# 99_CAN_Interface.net
KiCad netlist of a schematic drawn in Altium Designer
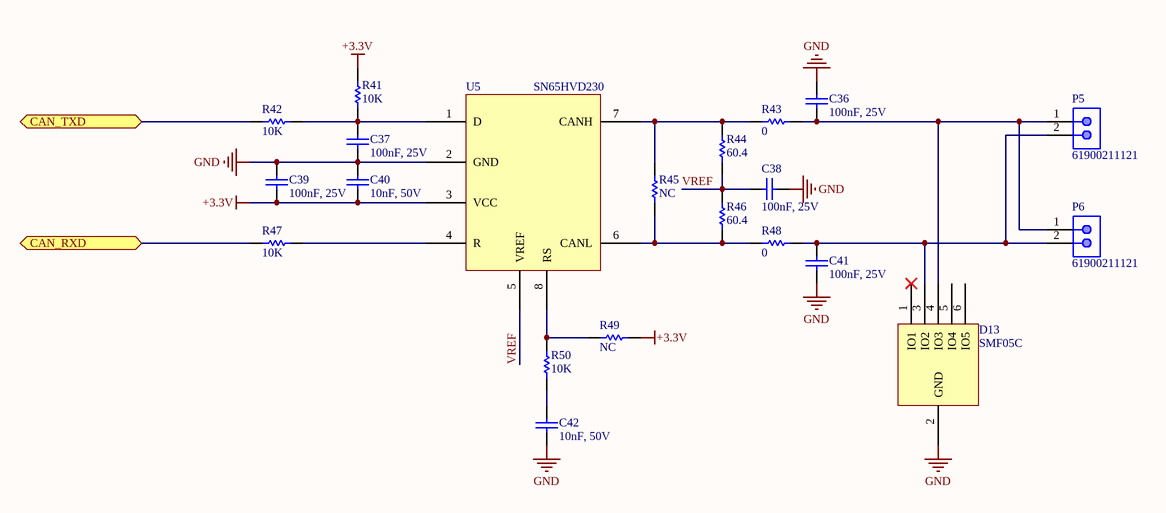
[diagram p0: 99_CAN_Interface.SchDoc]

(export (version "E")
  (design (tool "Eeschema 10.0.6"))
  (components
    (comp (ref "C36")
      (value "100nF, 25V")
      (footprint "WCAP-CSGP_0603_H=0.8mm_Reflow")
      (description "WCAP-CSGP Multilayer Ceramic Chip Capacitor, General Purpose, size 0603, X7R, 100nF, 25V")
      (fields
        (field (name "MANUFACTURER PART NUMBER") "885012206071")
        (field (name "MANUFACTURER") "Wurth Elektronik")
      )
      (libsource (lib "Altium_WCAP-CSGP (rev20a)") (part "885012206071"))
    )
    (comp (ref "C37")
      (value "100nF, 25V")
      (footprint "WCAP-CSGP_0603_H=0.8mm_Reflow")
      (description "WCAP-CSGP Multilayer Ceramic Chip Capacitor, General Purpose, size 0603, X7R, 100nF, 25V")
      (fields
        (field (name "MANUFACTURER PART NUMBER") "885012206071")
        (field (name "MANUFACTURER") "Wurth Elektronik")
      )
      (libsource (lib "Altium_WCAP-CSGP (rev20a)") (part "885012206071"))
    )
    (comp (ref "C38")
      (value "100nF, 25V")
      (footprint "WCAP-CSGP_0603_H=0.8mm_Reflow")
      (description "WCAP-CSGP Multilayer Ceramic Chip Capacitor, General Purpose, size 0603, X7R, 100nF, 25V")
      (fields
        (field (name "MANUFACTURER PART NUMBER") "885012206071")
        (field (name "MANUFACTURER") "Wurth Elektronik")
      )
      (libsource (lib "Altium_WCAP-CSGP (rev20a)") (part "885012206071"))
    )
    (comp (ref "C39")
      (value "100nF, 25V")
      (footprint "WCAP-CSGP_0603_H=0.8mm_Reflow")
      (description "WCAP-CSGP Multilayer Ceramic Chip Capacitor, General Purpose, size 0603, X7R, 100nF, 25V")
      (fields
        (field (name "MANUFACTURER PART NUMBER") "885012206071")
        (field (name "MANUFACTURER") "Wurth Elektronik")
      )
      (libsource (lib "Altium_WCAP-CSGP (rev20a)") (part "885012206071"))
    )
    (comp (ref "C40")
      (value "10nF, 50V")
      (footprint "WCAP-CSGP_0603_H=0.8mm_Reflow")
      (description "WCAP-CSGP Multilayer Ceramic Chip Capacitor, General Purpose, size 0603, X7R, 10nF, 50V")
      (fields
        (field (name "MANUFACTURER PART NUMBER") "885012206089")
        (field (name "MANUFACTURER") "Wurth Elektronik")
      )
      (libsource (lib "Altium_WCAP-CSGP (rev20a)") (part "885012206089"))
    )
    (comp (ref "C41")
      (value "100nF, 25V")
      (footprint "WCAP-CSGP_0603_H=0.8mm_Reflow")
      (description "WCAP-CSGP Multilayer Ceramic Chip Capacitor, General Purpose, size 0603, X7R, 100nF, 25V")
      (fields
        (field (name "MANUFACTURER PART NUMBER") "885012206071")
        (field (name "MANUFACTURER") "Wurth Elektronik")
      )
      (libsource (lib "Altium_WCAP-CSGP (rev20a)") (part "885012206071"))
    )
    (comp (ref "C42")
      (value "10nF, 50V")
      (footprint "WCAP-CSGP_0603_H=0.8mm_Reflow")
      (description "WCAP-CSGP Multilayer Ceramic Chip Capacitor, General Purpose, size 0603, X7R, 10nF, 50V")
      (fields
        (field (name "MANUFACTURER PART NUMBER") "885012206089")
        (field (name "MANUFACTURER") "Wurth Elektronik")
      )
      (libsource (lib "Altium_WCAP-CSGP (rev20a)") (part "885012206089"))
    )
    (comp (ref "D13")
      (value "SMF05C")
      (footprint "SOT65P210X110-6N")
      (libsource (lib "MiclsLib") (part "SMF05C"))
    )
    (comp (ref "P5")
      (value "61900211121")
      (footprint "61900211121")
      (description "WR-WTB THT Male Vertical Locking Header, pitch 2.54mm, 2p")
      (fields (field (name "PUBLISHER") "Wurth Elektronik"))
      (libsource (lib "653008114822_Altium_WR-WTB_rev20a") (part "61900211121"))
    )
    (comp (ref "P6")
      (value "61900211121")
      (footprint "61900211121")
      (description "WR-WTB THT Male Vertical Locking Header, pitch 2.54mm, 2p")
      (fields (field (name "PUBLISHER") "Wurth Elektronik"))
      (libsource (lib "653008114822_Altium_WR-WTB_rev20a") (part "61900211121"))
    )
    (comp (ref "R41")
      (value "10K")
      (footprint "RES-SM-0603")
      (description "Resistor")
      (fields (field (name "Comment") "RESISTOR SMD"))
      (libsource (lib "PIF_Library") (part "RESISTOR SMD"))
    )
    (comp (ref "R42")
      (value "10K")
      (footprint "RES-SM-0603")
      (description "Resistor")
      (fields (field (name "Comment") "RESISTOR SMD"))
      (libsource (lib "PIF_Library") (part "RESISTOR SMD"))
    )
    (comp (ref "R43")
      (value "0")
      (footprint "RES-SM-0603")
      (description "Resistor")
      (fields (field (name "Comment") "RESISTOR SMD"))
      (libsource (lib "PIF_Library") (part "RESISTOR SMD"))
    )
    (comp (ref "R44")
      (value "60.4")
      (footprint "RES-SM-0603")
      (description "Resistor")
      (fields (field (name "Comment") "RESISTOR SMD"))
      (libsource (lib "PIF_Library") (part "RESISTOR SMD"))
    )
    (comp (ref "R45")
      (value "NC")
      (footprint "RES-SM-0603")
      (description "Resistor")
      (fields (field (name "Comment") "RESISTOR SMD"))
      (libsource (lib "PIF_Library") (part "RESISTOR SMD"))
    )
    (comp (ref "R46")
      (value "60.4")
      (footprint "RES-SM-0603")
      (description "Resistor")
      (fields (field (name "Comment") "RESISTOR SMD"))
      (libsource (lib "PIF_Library") (part "RESISTOR SMD"))
    )
    (comp (ref "R47")
      (value "10K")
      (footprint "RES-SM-0603")
      (description "Resistor")
      (fields (field (name "Comment") "RESISTOR SMD"))
      (libsource (lib "PIF_Library") (part "RESISTOR SMD"))
    )
    (comp (ref "R48")
      (value "0")
      (footprint "RES-SM-0603")
      (description "Resistor")
      (fields (field (name "Comment") "RESISTOR SMD"))
      (libsource (lib "PIF_Library") (part "RESISTOR SMD"))
    )
    (comp (ref "R49")
      (value "NC")
      (footprint "RES-SM-0603")
      (description "Resistor")
      (fields (field (name "Comment") "RESISTOR SMD"))
      (libsource (lib "PIF_Library") (part "RESISTOR SMD"))
    )
    (comp (ref "R50")
      (value "10K")
      (footprint "RES-SM-0603")
      (description "Resistor")
      (fields (field (name "Comment") "RESISTOR SMD"))
      (libsource (lib "PIF_Library") (part "RESISTOR SMD"))
    )
    (comp (ref "U5")
      (value "SN65HVD230")
      (footprint "SOIC127P600X175-8N")
      (libsource (lib "MiclsLib") (part "SN65HVD230"))
    )
  )
  (nets
    (net (code "1") (name "+3.3V") (class "Default")
      (node (ref "C39") (pin "1") (pinfunction "1_1") (pintype "passive"))
      (node (ref "C40") (pin "1") (pinfunction "1_1") (pintype "passive"))
      (node (ref "R41") (pin "2") (pinfunction "2_2") (pintype "passive"))
      (node (ref "R49") (pin "1") (pinfunction "1_1") (pintype "passive"))
      (node (ref "U5") (pin "3") (pinfunction "VCC_3") (pintype "passive"))
    )
    (net (code "2") (name "/CAN_RXD") (class "Default")
      (node (ref "R47") (pin "2") (pinfunction "2_2") (pintype "passive"))
    )
    (net (code "3") (name "/CAN_TXD") (class "Default")
      (node (ref "R42") (pin "2") (pinfunction "2_2") (pintype "passive"))
    )
    (net (code "4") (name "/VREF") (class "Default")
      (node (ref "C38") (pin "2") (pinfunction "2_2") (pintype "passive"))
      (node (ref "R44") (pin "2") (pinfunction "2_2") (pintype "passive"))
      (node (ref "R46") (pin "1") (pinfunction "1_1") (pintype "passive"))
      (node (ref "U5") (pin "5") (pinfunction "VREF_5") (pintype "passive"))
    )
    (net (code "5") (name "GND") (class "Default")
      (node (ref "C36") (pin "2") (pinfunction "2_2") (pintype "passive"))
      (node (ref "C37") (pin "1") (pinfunction "1_1") (pintype "passive"))
      (node (ref "C38") (pin "1") (pinfunction "1_1") (pintype "passive"))
      (node (ref "C39") (pin "2") (pinfunction "2_2") (pintype "passive"))
      (node (ref "C40") (pin "2") (pinfunction "2_2") (pintype "passive"))
      (node (ref "C41") (pin "1") (pinfunction "1_1") (pintype "passive"))
      (node (ref "C42") (pin "1") (pinfunction "1_1") (pintype "passive"))
      (node (ref "D13") (pin "2") (pinfunction "GND_2") (pintype "passive"))
      (node (ref "U5") (pin "2") (pinfunction "GND_2") (pintype "passive"))
    )
    (net (code "6") (name "Net-(C42-Pad2)") (class "Default")
      (node (ref "C42") (pin "2") (pinfunction "2_2") (pintype "passive"))
      (node (ref "R50") (pin "1") (pinfunction "1_1") (pintype "passive"))
    )
    (net (code "7") (name "Net-(D13-IO2)") (class "Default")
      (node (ref "C41") (pin "2") (pinfunction "2_2") (pintype "passive"))
      (node (ref "D13") (pin "3") (pinfunction "IO2_3") (pintype "passive"))
      (node (ref "P5") (pin "2") (pinfunction "2_2") (pintype "passive"))
      (node (ref "P6") (pin "2") (pinfunction "2_2") (pintype "passive"))
      (node (ref "R48") (pin "1") (pinfunction "1_1") (pintype "passive"))
    )
    (net (code "8") (name "Net-(D13-IO3)") (class "Default")
      (node (ref "C36") (pin "1") (pinfunction "1_1") (pintype "passive"))
      (node (ref "D13") (pin "4") (pinfunction "IO3_4") (pintype "passive"))
      (node (ref "P5") (pin "1") (pinfunction "1_1") (pintype "passive"))
      (node (ref "P6") (pin "1") (pinfunction "1_1") (pintype "passive"))
      (node (ref "R43") (pin "1") (pinfunction "1_1") (pintype "passive"))
    )
    (net (code "9") (name "Net-(U5-CANH)") (class "Default")
      (node (ref "R43") (pin "2") (pinfunction "2_2") (pintype "passive"))
      (node (ref "R44") (pin "1") (pinfunction "1_1") (pintype "passive"))
      (node (ref "R45") (pin "1") (pinfunction "1_1") (pintype "passive"))
      (node (ref "U5") (pin "7") (pinfunction "CANH_7") (pintype "passive"))
    )
    (net (code "10") (name "Net-(U5-CANL)") (class "Default")
      (node (ref "R45") (pin "2") (pinfunction "2_2") (pintype "passive"))
      (node (ref "R46") (pin "2") (pinfunction "2_2") (pintype "passive"))
      (node (ref "R48") (pin "2") (pinfunction "2_2") (pintype "passive"))
      (node (ref "U5") (pin "6") (pinfunction "CANL_6") (pintype "passive"))
    )
    (net (code "11") (name "Net-(U5-D)") (class "Default")
      (node (ref "C37") (pin "2") (pinfunction "2_2") (pintype "passive"))
      (node (ref "R41") (pin "1") (pinfunction "1_1") (pintype "passive"))
      (node (ref "R42") (pin "1") (pinfunction "1_1") (pintype "passive"))
      (node (ref "U5") (pin "1") (pinfunction "D_1") (pintype "passive"))
    )
    (net (code "12") (name "Net-(U5-R)") (class "Default")
      (node (ref "R47") (pin "1") (pinfunction "1_1") (pintype "passive"))
      (node (ref "U5") (pin "4") (pinfunction "R_4") (pintype "passive"))
    )
    (net (code "13") (name "Net-(U5-RS)") (class "Default")
      (node (ref "R49") (pin "2") (pinfunction "2_2") (pintype "passive"))
      (node (ref "R50") (pin "2") (pinfunction "2_2") (pintype "passive"))
      (node (ref "U5") (pin "8") (pinfunction "RS_8") (pintype "passive"))
    )
    (net (code "14") (name "unconnected-(D13-IO1-Pad1)") (class "Default")
      (node (ref "D13") (pin "1") (pinfunction "IO1_1") (pintype "passive+no_connect"))
    )
    (net (code "15") (name "unconnected-(D13-IO4-Pad5)") (class "Default")
      (node (ref "D13") (pin "5") (pinfunction "IO4_5") (pintype "passive"))
    )
    (net (code "16") (name "unconnected-(D13-IO5-Pad6)") (class "Default")
      (node (ref "D13") (pin "6") (pinfunction "IO5_6") (pintype "passive"))
    )
  )
)
